# MolunSmartHomeKits_2021-06-21.net
KiCad netlist of a schematic drawn in EasyEDA
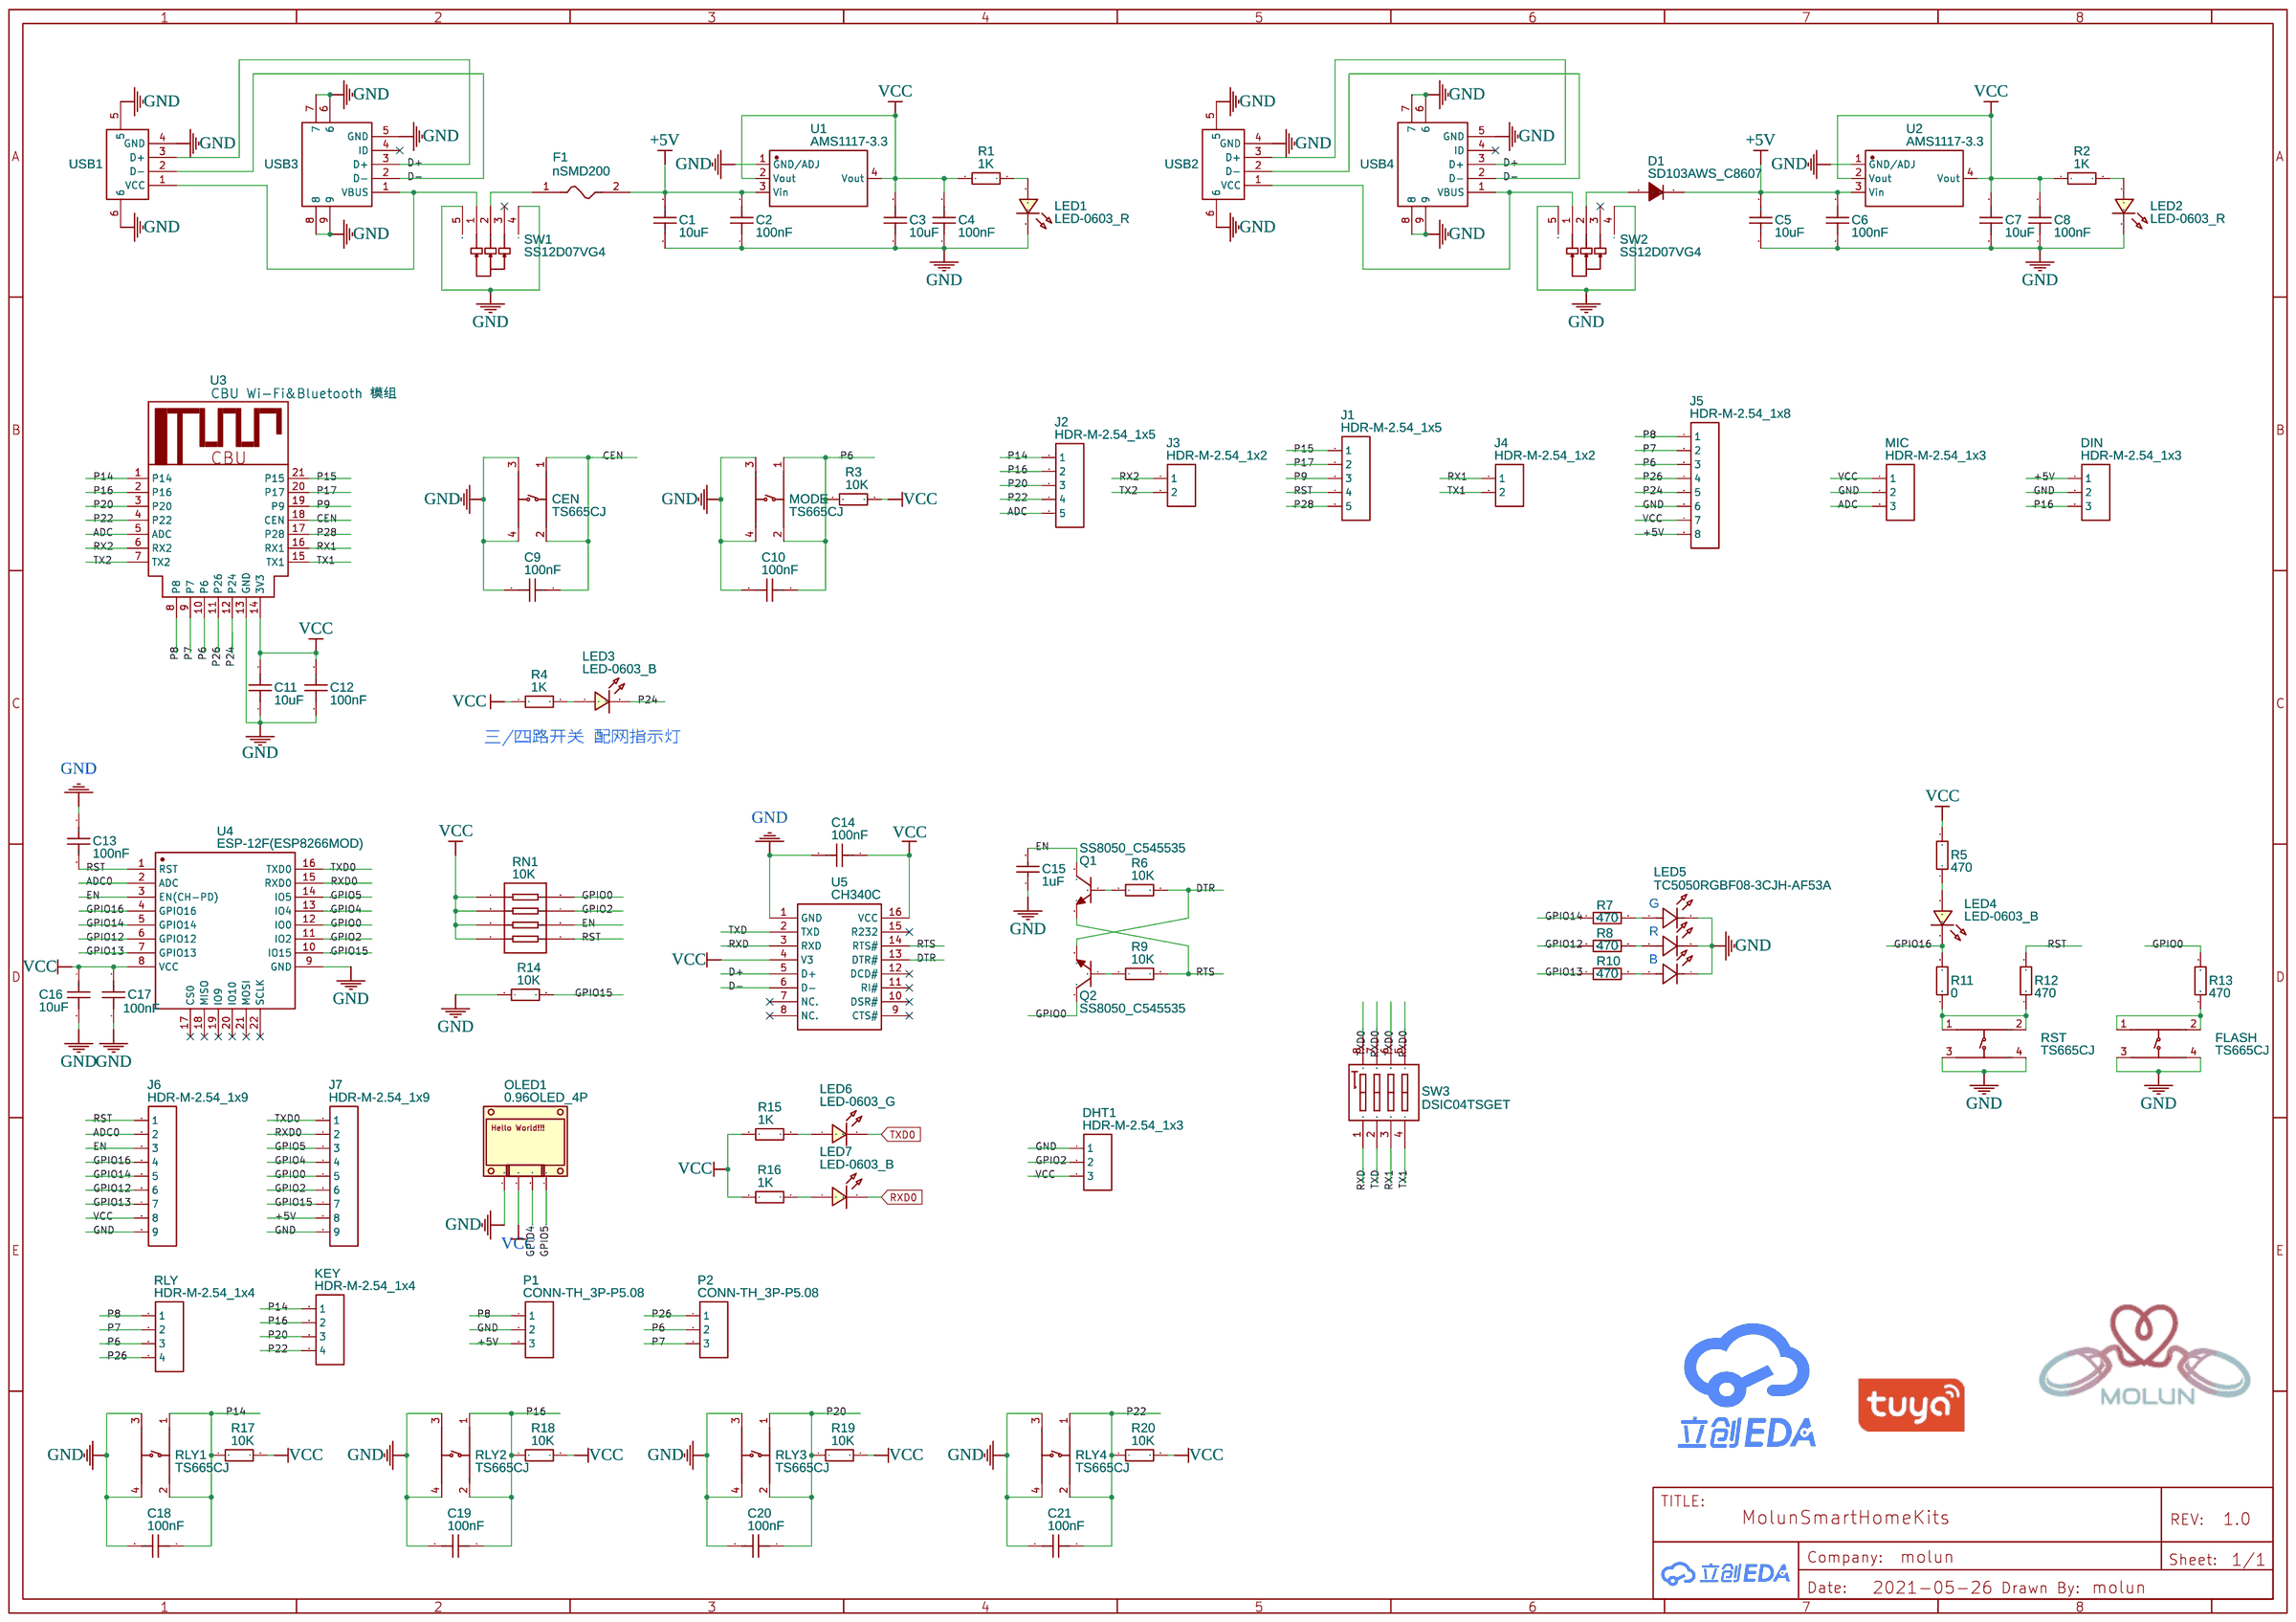
[diagram p0: MolunSmartHomeKits]
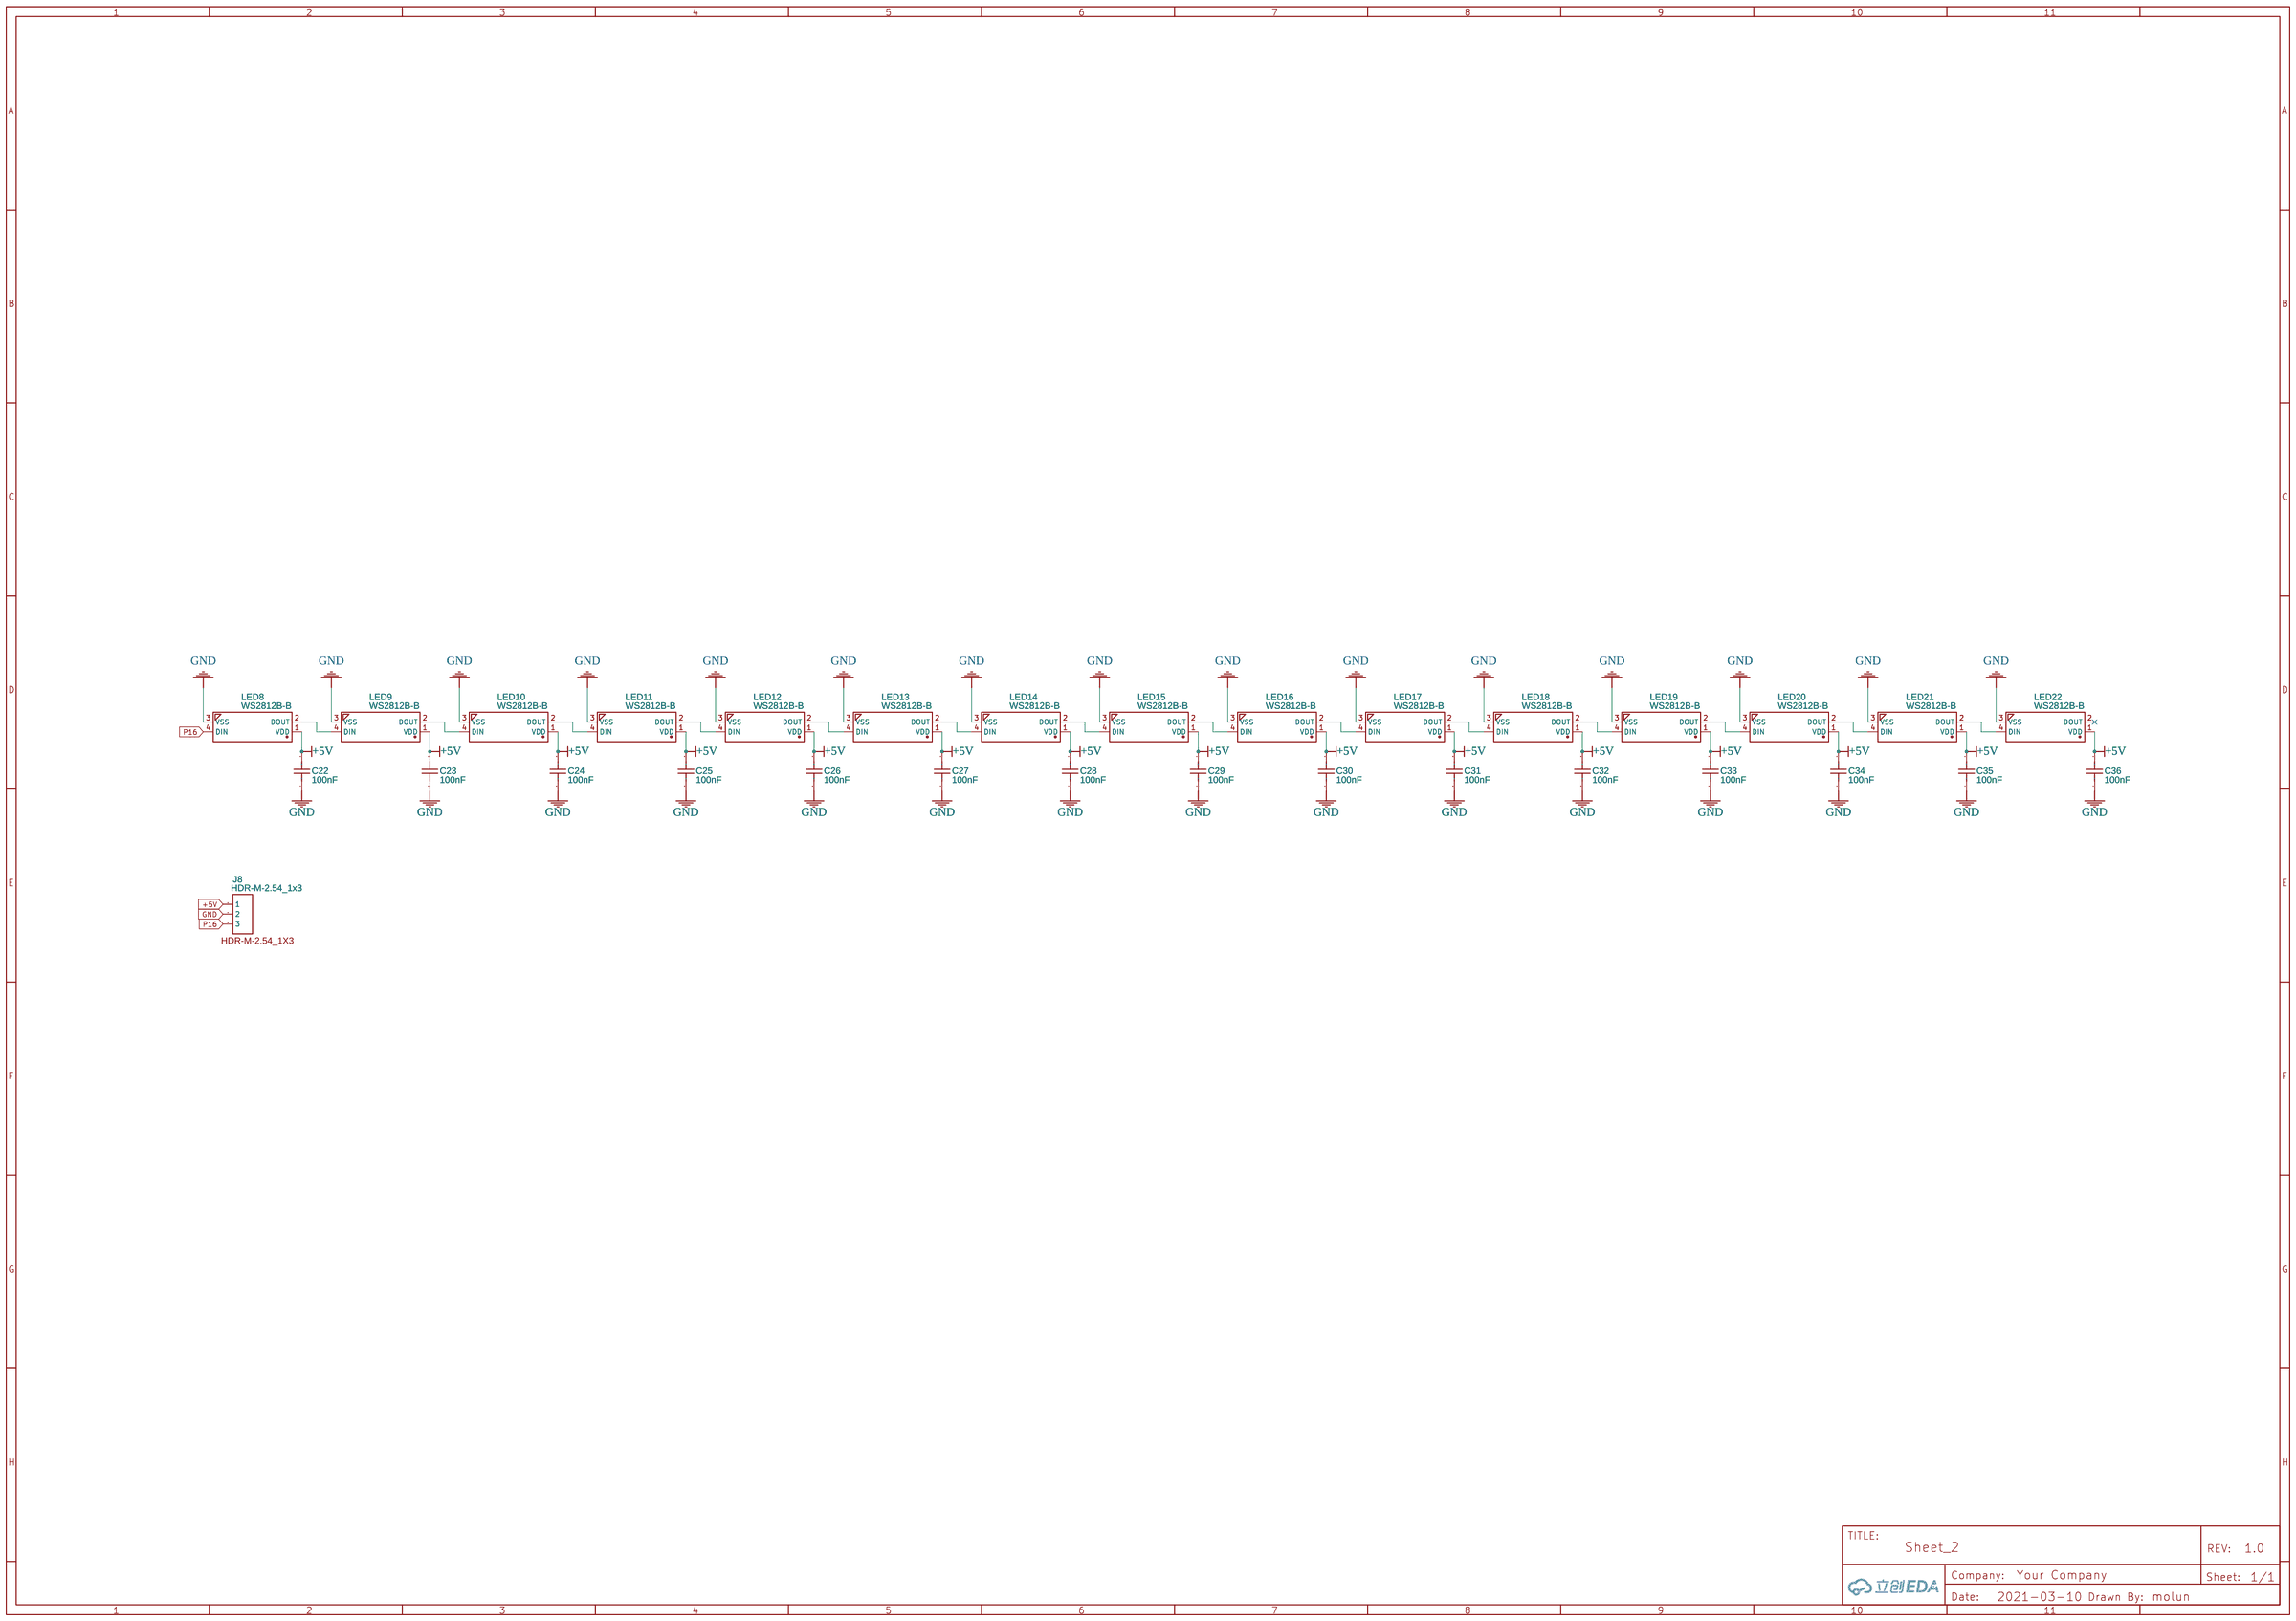
[diagram p1: 4合1_WS2812B圆环灯板]

(export (version "E")
  (design (tool "Eeschema 10.0.6"))
  (components
    (comp (ref "C1")
      (value "10uF")
      (fields
        (field (name "BOM_Manufacturer Part") "CC0603KRX5R6BB106")
        (field (name "BOM_Supplier Part") "C326057")
      )
      (libsource (lib "") (part "CC0603KRX5R6BB106"))
    )
    (comp (ref "C2")
      (value "100nF")
      (fields
        (field (name "BOM_Manufacturer Part") "AC0603KRX7R9BB104")
        (field (name "BOM_Supplier Part") "C149620")
      )
      (libsource (lib "") (part "AC0603KRX7R9BB104"))
    )
    (comp (ref "C3")
      (value "10uF")
      (fields
        (field (name "BOM_Manufacturer Part") "CC0603KRX5R6BB106")
        (field (name "BOM_Supplier Part") "C326057")
      )
      (libsource (lib "") (part "CC0603KRX5R6BB106"))
    )
    (comp (ref "C4")
      (value "100nF")
      (fields
        (field (name "BOM_Manufacturer Part") "AC0603KRX7R9BB104")
        (field (name "BOM_Supplier Part") "C149620")
      )
      (libsource (lib "") (part "AC0603KRX7R9BB104"))
    )
    (comp (ref "C5")
      (value "10uF")
      (fields
        (field (name "BOM_Manufacturer Part") "CC0603KRX5R6BB106")
        (field (name "BOM_Supplier Part") "C326057")
      )
      (libsource (lib "") (part "CC0603KRX5R6BB106"))
    )
    (comp (ref "C6")
      (value "100nF")
      (fields
        (field (name "BOM_Manufacturer Part") "AC0603KRX7R9BB104")
        (field (name "BOM_Supplier Part") "C149620")
      )
      (libsource (lib "") (part "AC0603KRX7R9BB104"))
    )
    (comp (ref "C7")
      (value "10uF")
      (fields
        (field (name "BOM_Manufacturer Part") "CC0603KRX5R6BB106")
        (field (name "BOM_Supplier Part") "C326057")
      )
      (libsource (lib "") (part "CC0603KRX5R6BB106"))
    )
    (comp (ref "C8")
      (value "100nF")
      (fields
        (field (name "BOM_Manufacturer Part") "AC0603KRX7R9BB104")
        (field (name "BOM_Supplier Part") "C149620")
      )
      (libsource (lib "") (part "AC0603KRX7R9BB104"))
    )
    (comp (ref "C9")
      (value "100nF")
      (fields
        (field (name "BOM_Manufacturer Part") "CC0603KRX7R7BB104")
        (field (name "BOM_Supplier Part") "C108079")
      )
      (libsource (lib "") (part "CC0603KRX7R7BB104_1"))
    )
    (comp (ref "C10")
      (value "100nF")
      (fields
        (field (name "BOM_Manufacturer Part") "CC0603KRX7R7BB104")
        (field (name "BOM_Supplier Part") "C108079")
      )
      (libsource (lib "") (part "CC0603KRX7R7BB104_1"))
    )
    (comp (ref "C11")
      (value "10uF")
      (fields
        (field (name "BOM_Manufacturer Part") "CL10A106MQ8NNNC")
        (field (name "BOM_Supplier Part") "C1691")
      )
      (libsource (lib "") (part "CL10A106MQ8NNNC"))
    )
    (comp (ref "C12")
      (value "100nF")
      (fields
        (field (name "BOM_Manufacturer Part") "CC0603KRX7R7BB104")
        (field (name "BOM_Supplier Part") "C108079")
      )
      (libsource (lib "") (part "CC0603KRX7R7BB104"))
    )
    (comp (ref "C13")
      (value "100nF")
      (fields
        (field (name "BOM_Manufacturer Part") "CC0603KRX7R7BB104")
        (field (name "BOM_Supplier Part") "C108079")
      )
      (libsource (lib "") (part "CC0603KRX7R7BB104_2"))
    )
    (comp (ref "C14")
      (value "100nF")
      (fields
        (field (name "BOM_Manufacturer Part") "AC0603KRX7R9BB104")
        (field (name "BOM_Supplier Part") "C149620")
      )
      (libsource (lib "") (part "AC0603KRX7R9BB104_1"))
    )
    (comp (ref "C15")
      (value "1uF")
      (fields
        (field (name "BOM_Manufacturer Part") "CC0603KRX5R7BB105")
        (field (name "BOM_Supplier Part") "C106215")
      )
      (libsource (lib "") (part "CC0603KRX5R7BB105"))
    )
    (comp (ref "C16")
      (value "10uF")
      (fields
        (field (name "BOM_Manufacturer Part") "CL10A106MQ8NNNC")
        (field (name "BOM_Supplier Part") "C1691")
      )
      (libsource (lib "") (part "CL10A106MQ8NNNC"))
    )
    (comp (ref "C17")
      (value "100nF")
      (fields
        (field (name "BOM_Manufacturer Part") "CC0603KRX7R7BB104")
        (field (name "BOM_Supplier Part") "C108079")
      )
      (libsource (lib "") (part "CC0603KRX7R7BB104"))
    )
    (comp (ref "C18")
      (value "100nF")
      (fields
        (field (name "BOM_Manufacturer Part") "CC0603KRX7R7BB104")
        (field (name "BOM_Supplier Part") "C108079")
      )
      (libsource (lib "") (part "CC0603KRX7R7BB104_1"))
    )
    (comp (ref "C19")
      (value "100nF")
      (fields
        (field (name "BOM_Manufacturer Part") "CC0603KRX7R7BB104")
        (field (name "BOM_Supplier Part") "C108079")
      )
      (libsource (lib "") (part "CC0603KRX7R7BB104_1"))
    )
    (comp (ref "C20")
      (value "100nF")
      (fields
        (field (name "BOM_Manufacturer Part") "CC0603KRX7R7BB104")
        (field (name "BOM_Supplier Part") "C108079")
      )
      (libsource (lib "") (part "CC0603KRX7R7BB104_1"))
    )
    (comp (ref "C21")
      (value "100nF")
      (fields
        (field (name "BOM_Manufacturer Part") "CC0603KRX7R7BB104")
        (field (name "BOM_Supplier Part") "C108079")
      )
      (libsource (lib "") (part "CC0603KRX7R7BB104_1"))
    )
    (comp (ref "CEN")
      (value "TS665CJ")
      (fields (field (name "BOM_Supplier Part") "C393938"))
      (libsource (lib "") (part "TS665CJ_2"))
    )
    (comp (ref "D1")
      (value "SD103AWS_C8607")
      (fields (field (name "BOM_Manufacturer Part") "SD103AWS") (field (name "BOM_Supplier Part") "C8607"))
      (libsource (lib "") (part "SD103AWS_C8607"))
    )
    (comp (ref "DHT1")
      (value "HDR-M-2.54_1x3")
      (fields (field (name "BOM_Supplier Part") "C180248"))
      (libsource (lib "") (part "HDR-M-2.54_1x3_2"))
    )
    (comp (ref "DIN")
      (value "HDR-M-2.54_1x3")
      (fields (field (name "BOM_Supplier Part") "C180248"))
      (libsource (lib "") (part "HDR-M-2.54_1x3_1"))
    )
    (comp (ref "F1")
      (value "nSMD200")
      (fields (field (name "BOM_Supplier Part") "C70085"))
      (libsource (lib "") (part "nSMD200"))
    )
    (comp (ref "FLASH")
      (value "TS665CJ")
      (fields (field (name "BOM_Supplier Part") "C393938"))
      (libsource (lib "") (part "TS665CJ_4"))
    )
    (comp (ref "J1")
      (value "HDR-M-2.54_1x5")
      (fields (field (name "BOM_Supplier Part") "C358687"))
      (libsource (lib "") (part "HDR-M-2.54_1x5"))
    )
    (comp (ref "J2")
      (value "HDR-M-2.54_1x5")
      (fields (field (name "BOM_Supplier Part") "C358687"))
      (libsource (lib "") (part "HDR-M-2.54_1x5"))
    )
    (comp (ref "J3")
      (value "HDR-M-2.54_1x2")
      (fields (field (name "BOM_Supplier Part") "C124375"))
      (libsource (lib "") (part "HDR-M-2.54_1x2"))
    )
    (comp (ref "J4")
      (value "HDR-M-2.54_1x2")
      (fields (field (name "BOM_Supplier Part") "C124375"))
      (libsource (lib "") (part "HDR-M-2.54_1x2"))
    )
    (comp (ref "J5")
      (value "HDR-M-2.54_1x8")
      (fields (field (name "BOM_Supplier Part") "C190820"))
      (libsource (lib "") (part "HDR-M-2.54_1x8"))
    )
    (comp (ref "J6")
      (value "HDR-M-2.54_1x9")
      (fields (field (name "BOM_Supplier Part") "C225484"))
      (libsource (lib "") (part "HDR-M-2.54_1x9"))
    )
    (comp (ref "J7")
      (value "HDR-M-2.54_1x9")
      (fields (field (name "BOM_Supplier Part") "C225484"))
      (libsource (lib "") (part "HDR-M-2.54_1x9"))
    )
    (comp (ref "KEY")
      (value "HDR-M-2.54_1x4")
      (fields (field (name "BOM_Supplier Part") "C124378"))
      (libsource (lib "") (part "HDR-M-2.54_1x4_1"))
    )
    (comp (ref "LED1")
      (value "LED-0603_R")
      (fields
        (field (name "BOM_Manufacturer Part") "19-217/R6C-AL1M2VY/3T")
        (field (name "BOM_Supplier Part") "C72044")
      )
      (libsource (lib "") (part "LED-0603_R"))
    )
    (comp (ref "LED2")
      (value "LED-0603_R")
      (fields
        (field (name "BOM_Manufacturer Part") "19-217/R6C-AL1M2VY/3T")
        (field (name "BOM_Supplier Part") "C72044")
      )
      (libsource (lib "") (part "LED-0603_R"))
    )
    (comp (ref "LED3")
      (value "LED-0603_B")
      (fields
        (field (name "BOM_Manufacturer Part") "19-217/BHC-ZL1M2RY/3T")
        (field (name "BOM_Supplier Part") "C72041")
      )
      (libsource (lib "") (part "LED-0603_B"))
    )
    (comp (ref "LED4")
      (value "LED-0603_B")
      (fields
        (field (name "BOM_Manufacturer Part") "19-217/BHC-ZL1M2RY/3T")
        (field (name "BOM_Supplier Part") "C72041")
      )
      (libsource (lib "") (part "LED-0603_B_1"))
    )
    (comp (ref "LED5")
      (value "TC5050RGBF08-3CJH-AF53A")
      (fields (field (name "BOM_Supplier Part") "C784540"))
      (libsource (lib "") (part "TC5050RGBF08-3CJH-AF53A"))
    )
    (comp (ref "LED6")
      (value "LED-0603_G")
      (fields
        (field (name "BOM_Manufacturer Part") "19-217/GHC-YR1S2/3T")
        (field (name "BOM_Supplier Part") "C72043")
      )
      (libsource (lib "") (part "LED-0603_G"))
    )
    (comp (ref "LED7")
      (value "LED-0603_B")
      (fields
        (field (name "BOM_Manufacturer Part") "19-217/BHC-ZL1M2RY/3T")
        (field (name "BOM_Supplier Part") "C72041")
      )
      (libsource (lib "") (part "LED-0603_B"))
    )
    (comp (ref "MIC")
      (value "HDR-M-2.54_1x3")
      (fields (field (name "BOM_Supplier Part") "C180248"))
      (libsource (lib "") (part "HDR-M-2.54_1x3"))
    )
    (comp (ref "MODE")
      (value "TS665CJ")
      (fields (field (name "BOM_Supplier Part") "C393938"))
      (libsource (lib "") (part "TS665CJ_1"))
    )
    (comp (ref "OLED1") (value "0.96OLED_4P") (libsource (lib "") (part "0.96OLED_4P")))
    (comp (ref "P1") (value "CONN-TH_3P-P5.08") (libsource (lib "") (part "CONN-TH_3P-P5.08")))
    (comp (ref "P2") (value "CONN-TH_3P-P5.08") (libsource (lib "") (part "CONN-TH_3P-P5.08")))
    (comp (ref "Q1")
      (value "SS8050_C545535")
      (fields (field (name "BOM_Manufacturer Part") "SS8050") (field (name "BOM_Supplier Part") "C545535"))
      (libsource (lib "") (part "SS8050_C545535"))
    )
    (comp (ref "Q2")
      (value "SS8050_C545535")
      (fields (field (name "BOM_Manufacturer Part") "SS8050") (field (name "BOM_Supplier Part") "C545535"))
      (libsource (lib "") (part "SS8050_C545535_1"))
    )
    (comp (ref "R1")
      (value "1K")
      (fields
        (field (name "BOM_Manufacturer Part") "0603WAF1001T5E")
        (field (name "BOM_Supplier Part") "C21190")
      )
      (libsource (lib "") (part "0603WAF1001T5E"))
    )
    (comp (ref "R2")
      (value "1K")
      (fields
        (field (name "BOM_Manufacturer Part") "0603WAF1001T5E")
        (field (name "BOM_Supplier Part") "C21190")
      )
      (libsource (lib "") (part "0603WAF1001T5E"))
    )
    (comp (ref "R3")
      (value "10K")
      (fields
        (field (name "BOM_Manufacturer Part") "0603WAJ0103T5E")
        (field (name "BOM_Supplier Part") "C15401")
      )
      (libsource (lib "") (part "0603WAJ0103T5E"))
    )
    (comp (ref "R4")
      (value "1K")
      (fields
        (field (name "BOM_Manufacturer Part") "0603WAF1001T5E")
        (field (name "BOM_Supplier Part") "C21190")
      )
      (libsource (lib "") (part "0603WAF1001T5E"))
    )
    (comp (ref "R5")
      (value "470")
      (fields
        (field (name "BOM_Manufacturer Part") "0603WAF4700T5E")
        (field (name "BOM_Supplier Part") "C23179")
      )
      (libsource (lib "") (part "0603WAF4700T5E"))
    )
    (comp (ref "R6")
      (value "10K")
      (fields
        (field (name "BOM_Manufacturer Part") "0603WAF1002T5E")
        (field (name "BOM_Supplier Part") "C25804")
      )
      (libsource (lib "") (part "0603WAF1002T5E"))
    )
    (comp (ref "R7")
      (value "470")
      (fields
        (field (name "BOM_Manufacturer Part") "0603WAF4700T5E")
        (field (name "BOM_Supplier Part") "C23179")
      )
      (libsource (lib "") (part "0603WAF4700T5E_1"))
    )
    (comp (ref "R8")
      (value "470")
      (fields
        (field (name "BOM_Manufacturer Part") "0603WAF4700T5E")
        (field (name "BOM_Supplier Part") "C23179")
      )
      (libsource (lib "") (part "0603WAF4700T5E_1"))
    )
    (comp (ref "R9")
      (value "10K")
      (fields
        (field (name "BOM_Manufacturer Part") "0603WAF1002T5E")
        (field (name "BOM_Supplier Part") "C25804")
      )
      (libsource (lib "") (part "0603WAF1002T5E"))
    )
    (comp (ref "R10")
      (value "470")
      (fields
        (field (name "BOM_Manufacturer Part") "0603WAF4700T5E")
        (field (name "BOM_Supplier Part") "C23179")
      )
      (libsource (lib "") (part "0603WAF4700T5E_1"))
    )
    (comp (ref "R11")
      (value "0")
      (fields
        (field (name "BOM_Manufacturer Part") "AECR0603F0000K9")
        (field (name "BOM_Supplier Part") "C328332")
      )
      (libsource (lib "") (part "AECR0603F0000K9"))
    )
    (comp (ref "R12")
      (value "470")
      (fields
        (field (name "BOM_Manufacturer Part") "0603WAF4700T5E")
        (field (name "BOM_Supplier Part") "C23179")
      )
      (libsource (lib "") (part "0603WAF4700T5E"))
    )
    (comp (ref "R13")
      (value "470")
      (fields
        (field (name "BOM_Manufacturer Part") "0603WAF4700T5E")
        (field (name "BOM_Supplier Part") "C23179")
      )
      (libsource (lib "") (part "0603WAF4700T5E"))
    )
    (comp (ref "R14")
      (value "10K")
      (fields
        (field (name "BOM_Manufacturer Part") "0603WAF1002T5E")
        (field (name "BOM_Supplier Part") "C25804")
      )
      (libsource (lib "") (part "0603WAF1002T5E"))
    )
    (comp (ref "R15")
      (value "1K")
      (fields
        (field (name "BOM_Manufacturer Part") "0603WAF1001T5E")
        (field (name "BOM_Supplier Part") "C21190")
      )
      (libsource (lib "") (part "0603WAF1001T5E"))
    )
    (comp (ref "R16")
      (value "1K")
      (fields
        (field (name "BOM_Manufacturer Part") "0603WAF1001T5E")
        (field (name "BOM_Supplier Part") "C21190")
      )
      (libsource (lib "") (part "0603WAF1001T5E"))
    )
    (comp (ref "R17")
      (value "10K")
      (fields
        (field (name "BOM_Manufacturer Part") "0603WAJ0103T5E")
        (field (name "BOM_Supplier Part") "C15401")
      )
      (libsource (lib "") (part "0603WAJ0103T5E"))
    )
    (comp (ref "R18")
      (value "10K")
      (fields
        (field (name "BOM_Manufacturer Part") "0603WAJ0103T5E")
        (field (name "BOM_Supplier Part") "C15401")
      )
      (libsource (lib "") (part "0603WAJ0103T5E"))
    )
    (comp (ref "R19")
      (value "10K")
      (fields
        (field (name "BOM_Manufacturer Part") "0603WAJ0103T5E")
        (field (name "BOM_Supplier Part") "C15401")
      )
      (libsource (lib "") (part "0603WAJ0103T5E"))
    )
    (comp (ref "R20")
      (value "10K")
      (fields
        (field (name "BOM_Manufacturer Part") "0603WAJ0103T5E")
        (field (name "BOM_Supplier Part") "C15401")
      )
      (libsource (lib "") (part "0603WAJ0103T5E"))
    )
    (comp (ref "RLY")
      (value "HDR-M-2.54_1x4")
      (fields (field (name "BOM_Supplier Part") "C124378"))
      (libsource (lib "") (part "HDR-M-2.54_1x4"))
    )
    (comp (ref "RLY1")
      (value "TS665CJ")
      (fields (field (name "BOM_Supplier Part") "C393938"))
      (libsource (lib "") (part "TS665CJ"))
    )
    (comp (ref "RLY2")
      (value "TS665CJ")
      (fields (field (name "BOM_Supplier Part") "C393938"))
      (libsource (lib "") (part "TS665CJ"))
    )
    (comp (ref "RLY3")
      (value "TS665CJ")
      (fields (field (name "BOM_Supplier Part") "C393938"))
      (libsource (lib "") (part "TS665CJ"))
    )
    (comp (ref "RLY4")
      (value "TS665CJ")
      (fields (field (name "BOM_Supplier Part") "C393938"))
      (libsource (lib "") (part "TS665CJ"))
    )
    (comp (ref "RN1")
      (value "10K")
      (fields
        (field (name "BOM_Manufacturer Part") "4D03WGJ0103T5E")
        (field (name "BOM_Supplier Part") "C29718")
      )
      (libsource (lib "") (part "4D03WGJ0103T5E"))
    )
    (comp (ref "RST")
      (value "TS665CJ")
      (fields (field (name "BOM_Supplier Part") "C393938"))
      (libsource (lib "") (part "TS665CJ_3"))
    )
    (comp (ref "SW1")
      (value "SS12D07VG4")
      (fields (field (name "BOM_Supplier Part") "C431546"))
      (libsource (lib "") (part "SS12D07VG4"))
    )
    (comp (ref "SW2")
      (value "SS12D07VG4")
      (fields (field (name "BOM_Supplier Part") "C431546"))
      (libsource (lib "") (part "SS12D07VG4"))
    )
    (comp (ref "SW3")
      (value "DSIC04TSGET")
      (fields (field (name "BOM_Supplier Part") "C126850"))
      (libsource (lib "") (part "DSIC04TSGET"))
    )
    (comp (ref "U1")
      (value "AMS1117-3.3")
      (fields (field (name "BOM_Supplier Part") "C6186"))
      (libsource (lib "") (part "AMS1117-3.3"))
    )
    (comp (ref "U2")
      (value "AMS1117-3.3")
      (fields (field (name "BOM_Supplier Part") "C6186"))
      (libsource (lib "") (part "AMS1117-3.3"))
    )
    (comp (ref "U3")
      (value "CBU Wi-Fi&Bluetooth 模组")
      (libsource (lib "") (part "CBU Wi-Fi&amp;Bluetooth 模组"))
    )
    (comp (ref "U4")
      (value "ESP-12F(ESP8266MOD)")
      (fields (field (name "BOM_Supplier Part") "C82891"))
      (libsource (lib "") (part "ESP-12F(ESP8266MOD)"))
    )
    (comp (ref "U5")
      (value "CH340C")
      (fields (field (name "BOM_Supplier Part") "C84681"))
      (libsource (lib "") (part "CH340C"))
    )
    (comp (ref "USB1")
      (value "U217-04XN-XXR84")
      (fields (field (name "BOM_Supplier Part") "C319178"))
      (libsource (lib "") (part "U217-04XN-XXR84"))
    )
    (comp (ref "USB2")
      (value "U217-04XN-XXR84")
      (fields (field (name "BOM_Supplier Part") "C319178"))
      (libsource (lib "") (part "U217-04XN-XXR84"))
    )
    (comp (ref "USB3")
      (value "U254-051T-4BH83-F1S")
      (fields (field (name "BOM_Supplier Part") "C397452"))
      (libsource (lib "") (part "U254-051T-4BH83-F1S"))
    )
    (comp (ref "USB4")
      (value "U254-051T-4BH83-F1S")
      (fields (field (name "BOM_Supplier Part") "C397452"))
      (libsource (lib "") (part "U254-051T-4BH83-F1S"))
    )
    (comp (ref "C22")
      (value "100nF")
      (fields
        (field (name "BOM_Manufacturer Part") "CC0603KRX7R7BB104")
        (field (name "BOM_Supplier Part") "C108079")
      )
      (libsource (lib "") (part "CC0603KRX7R7BB104"))
    )
    (comp (ref "C23")
      (value "100nF")
      (fields
        (field (name "BOM_Manufacturer Part") "CC0603KRX7R7BB104")
        (field (name "BOM_Supplier Part") "C108079")
      )
      (libsource (lib "") (part "CC0603KRX7R7BB104"))
    )
    (comp (ref "C24")
      (value "100nF")
      (fields
        (field (name "BOM_Manufacturer Part") "CC0603KRX7R7BB104")
        (field (name "BOM_Supplier Part") "C108079")
      )
      (libsource (lib "") (part "CC0603KRX7R7BB104"))
    )
    (comp (ref "C25")
      (value "100nF")
      (fields
        (field (name "BOM_Manufacturer Part") "CC0603KRX7R7BB104")
        (field (name "BOM_Supplier Part") "C108079")
      )
      (libsource (lib "") (part "CC0603KRX7R7BB104"))
    )
    (comp (ref "C26")
      (value "100nF")
      (fields
        (field (name "BOM_Manufacturer Part") "CC0603KRX7R7BB104")
        (field (name "BOM_Supplier Part") "C108079")
      )
      (libsource (lib "") (part "CC0603KRX7R7BB104"))
    )
    (comp (ref "C27")
      (value "100nF")
      (fields
        (field (name "BOM_Manufacturer Part") "CC0603KRX7R7BB104")
        (field (name "BOM_Supplier Part") "C108079")
      )
      (libsource (lib "") (part "CC0603KRX7R7BB104"))
    )
    (comp (ref "C28")
      (value "100nF")
      (fields
        (field (name "BOM_Manufacturer Part") "CC0603KRX7R7BB104")
        (field (name "BOM_Supplier Part") "C108079")
      )
      (libsource (lib "") (part "CC0603KRX7R7BB104"))
    )
    (comp (ref "C29")
      (value "100nF")
      (fields
        (field (name "BOM_Manufacturer Part") "CC0603KRX7R7BB104")
        (field (name "BOM_Supplier Part") "C108079")
      )
      (libsource (lib "") (part "CC0603KRX7R7BB104"))
    )
    (comp (ref "C30")
      (value "100nF")
      (fields
        (field (name "BOM_Manufacturer Part") "CC0603KRX7R7BB104")
        (field (name "BOM_Supplier Part") "C108079")
      )
      (libsource (lib "") (part "CC0603KRX7R7BB104"))
    )
    (comp (ref "C31")
      (value "100nF")
      (fields
        (field (name "BOM_Manufacturer Part") "CC0603KRX7R7BB104")
        (field (name "BOM_Supplier Part") "C108079")
      )
      (libsource (lib "") (part "CC0603KRX7R7BB104"))
    )
    (comp (ref "C32")
      (value "100nF")
      (fields
        (field (name "BOM_Manufacturer Part") "CC0603KRX7R7BB104")
        (field (name "BOM_Supplier Part") "C108079")
      )
      (libsource (lib "") (part "CC0603KRX7R7BB104"))
    )
    (comp (ref "C33")
      (value "100nF")
      (fields
        (field (name "BOM_Manufacturer Part") "CC0603KRX7R7BB104")
        (field (name "BOM_Supplier Part") "C108079")
      )
      (libsource (lib "") (part "CC0603KRX7R7BB104"))
    )
    (comp (ref "C34")
      (value "100nF")
      (fields
        (field (name "BOM_Manufacturer Part") "CC0603KRX7R7BB104")
        (field (name "BOM_Supplier Part") "C108079")
      )
      (libsource (lib "") (part "CC0603KRX7R7BB104"))
    )
    (comp (ref "C35")
      (value "100nF")
      (fields
        (field (name "BOM_Manufacturer Part") "CC0603KRX7R7BB104")
        (field (name "BOM_Supplier Part") "C108079")
      )
      (libsource (lib "") (part "CC0603KRX7R7BB104"))
    )
    (comp (ref "C36")
      (value "100nF")
      (fields
        (field (name "BOM_Manufacturer Part") "CC0603KRX7R7BB104")
        (field (name "BOM_Supplier Part") "C108079")
      )
      (libsource (lib "") (part "CC0603KRX7R7BB104"))
    )
    (comp (ref "J8")
      (value "HDR-M-2.54_1x3")
      (fields (field (name "BOM_Supplier Part") "C180248"))
      (libsource (lib "") (part "HDR-M-2.54_1x3"))
    )
    (comp (ref "LED8")
      (value "WS2812B-B")
      (fields (field (name "BOM_Supplier Part") "C114586"))
      (libsource (lib "") (part "WS2812B-B"))
    )
    (comp (ref "LED9")
      (value "WS2812B-B")
      (fields (field (name "BOM_Supplier Part") "C114586"))
      (libsource (lib "") (part "WS2812B-B"))
    )
    (comp (ref "LED10")
      (value "WS2812B-B")
      (fields (field (name "BOM_Supplier Part") "C114586"))
      (libsource (lib "") (part "WS2812B-B"))
    )
    (comp (ref "LED11")
      (value "WS2812B-B")
      (fields (field (name "BOM_Supplier Part") "C114586"))
      (libsource (lib "") (part "WS2812B-B"))
    )
    (comp (ref "LED12")
      (value "WS2812B-B")
      (fields (field (name "BOM_Supplier Part") "C114586"))
      (libsource (lib "") (part "WS2812B-B"))
    )
    (comp (ref "LED13")
      (value "WS2812B-B")
      (fields (field (name "BOM_Supplier Part") "C114586"))
      (libsource (lib "") (part "WS2812B-B"))
    )
    (comp (ref "LED14")
      (value "WS2812B-B")
      (fields (field (name "BOM_Supplier Part") "C114586"))
      (libsource (lib "") (part "WS2812B-B"))
    )
    (comp (ref "LED15")
      (value "WS2812B-B")
      (fields (field (name "BOM_Supplier Part") "C114586"))
      (libsource (lib "") (part "WS2812B-B"))
    )
    (comp (ref "LED16")
      (value "WS2812B-B")
      (fields (field (name "BOM_Supplier Part") "C114586"))
      (libsource (lib "") (part "WS2812B-B"))
    )
    (comp (ref "LED17")
      (value "WS2812B-B")
      (fields (field (name "BOM_Supplier Part") "C114586"))
      (libsource (lib "") (part "WS2812B-B"))
    )
    (comp (ref "LED18")
      (value "WS2812B-B")
      (fields (field (name "BOM_Supplier Part") "C114586"))
      (libsource (lib "") (part "WS2812B-B"))
    )
    (comp (ref "LED19")
      (value "WS2812B-B")
      (fields (field (name "BOM_Supplier Part") "C114586"))
      (libsource (lib "") (part "WS2812B-B"))
    )
    (comp (ref "LED20")
      (value "WS2812B-B")
      (fields (field (name "BOM_Supplier Part") "C114586"))
      (libsource (lib "") (part "WS2812B-B"))
    )
    (comp (ref "LED21")
      (value "WS2812B-B")
      (fields (field (name "BOM_Supplier Part") "C114586"))
      (libsource (lib "") (part "WS2812B-B"))
    )
    (comp (ref "LED22")
      (value "WS2812B-B")
      (fields (field (name "BOM_Supplier Part") "C114586"))
      (libsource (lib "") (part "WS2812B-B"))
    )
  )
  (nets
    (net (code "1") (name "+5V") (class "Default")
      (node (ref "C1") (pin "2") (pinfunction "2_2") (pintype "unspecified"))
      (node (ref "C2") (pin "2") (pinfunction "2_2") (pintype "unspecified"))
      (node (ref "C22") (pin "2") (pinfunction "2_2") (pintype "unspecified"))
      (node (ref "C23") (pin "2") (pinfunction "2_2") (pintype "unspecified"))
      (node (ref "C24") (pin "2") (pinfunction "2_2") (pintype "unspecified"))
      (node (ref "C25") (pin "2") (pinfunction "2_2") (pintype "unspecified"))
      (node (ref "C26") (pin "2") (pinfunction "2_2") (pintype "unspecified"))
      (node (ref "C27") (pin "2") (pinfunction "2_2") (pintype "unspecified"))
      (node (ref "C28") (pin "2") (pinfunction "2_2") (pintype "unspecified"))
      (node (ref "C29") (pin "2") (pinfunction "2_2") (pintype "unspecified"))
      (node (ref "C30") (pin "2") (pinfunction "2_2") (pintype "unspecified"))
      (node (ref "C31") (pin "2") (pinfunction "2_2") (pintype "unspecified"))
      (node (ref "C32") (pin "2") (pinfunction "2_2") (pintype "unspecified"))
      (node (ref "C33") (pin "2") (pinfunction "2_2") (pintype "unspecified"))
      (node (ref "C34") (pin "2") (pinfunction "2_2") (pintype "unspecified"))
      (node (ref "C35") (pin "2") (pinfunction "2_2") (pintype "unspecified"))
      (node (ref "C36") (pin "2") (pinfunction "2_2") (pintype "unspecified"))
      (node (ref "C5") (pin "2") (pinfunction "2_2") (pintype "unspecified"))
      (node (ref "C6") (pin "2") (pinfunction "2_2") (pintype "unspecified"))
      (node (ref "D1") (pin "1") (pinfunction "C_1") (pintype "unspecified"))
      (node (ref "DIN") (pin "1") (pinfunction "1_1") (pintype "input"))
      (node (ref "F1") (pin "2") (pinfunction "2_2") (pintype "unspecified"))
      (node (ref "J5") (pin "8") (pinfunction "8_8") (pintype "unspecified"))
      (node (ref "J7") (pin "8") (pinfunction "8_8") (pintype "unspecified"))
      (node (ref "J8") (pin "1") (pinfunction "1_1") (pintype "input"))
      (node (ref "LED10") (pin "1") (pinfunction "VDD_1") (pintype "unspecified"))
      (node (ref "LED11") (pin "1") (pinfunction "VDD_1") (pintype "unspecified"))
      (node (ref "LED12") (pin "1") (pinfunction "VDD_1") (pintype "unspecified"))
      (node (ref "LED13") (pin "1") (pinfunction "VDD_1") (pintype "unspecified"))
      (node (ref "LED14") (pin "1") (pinfunction "VDD_1") (pintype "unspecified"))
      (node (ref "LED15") (pin "1") (pinfunction "VDD_1") (pintype "unspecified"))
      (node (ref "LED16") (pin "1") (pinfunction "VDD_1") (pintype "unspecified"))
      (node (ref "LED17") (pin "1") (pinfunction "VDD_1") (pintype "unspecified"))
      (node (ref "LED18") (pin "1") (pinfunction "VDD_1") (pintype "unspecified"))
      (node (ref "LED19") (pin "1") (pinfunction "VDD_1") (pintype "unspecified"))
      (node (ref "LED20") (pin "1") (pinfunction "VDD_1") (pintype "unspecified"))
      (node (ref "LED21") (pin "1") (pinfunction "VDD_1") (pintype "unspecified"))
      (node (ref "LED22") (pin "1") (pinfunction "VDD_1") (pintype "unspecified"))
      (node (ref "LED8") (pin "1") (pinfunction "VDD_1") (pintype "unspecified"))
      (node (ref "LED9") (pin "1") (pinfunction "VDD_1") (pintype "unspecified"))
      (node (ref "P1") (pin "3") (pinfunction "3_3") (pintype "unspecified"))
      (node (ref "U1") (pin "3") (pinfunction "Vin_3") (pintype "unspecified"))
      (node (ref "U2") (pin "3") (pinfunction "Vin_3") (pintype "unspecified"))
    )
    (net (code "2") (name "ADC") (class "Default")
      (node (ref "J2") (pin "5") (pinfunction "5_5") (pintype "unspecified"))
      (node (ref "MIC") (pin "3") (pinfunction "3_3") (pintype "input"))
      (node (ref "U3") (pin "5") (pinfunction "ADC_5") (pintype "bidirectional"))
    )
    (net (code "3") (name "ADC0") (class "Default")
      (node (ref "J6") (pin "2") (pinfunction "2_2") (pintype "unspecified"))
      (node (ref "U4") (pin "2") (pinfunction "ADC_2") (pintype "unspecified"))
    )
    (net (code "4") (name "CEN") (class "Default")
      (node (ref "C9") (pin "1") (pinfunction "1_1") (pintype "unspecified"))
      (node (ref "CEN") (pin "1") (pinfunction "A_1") (pintype "unspecified"))
      (node (ref "CEN") (pin "2") (pinfunction "B_2") (pintype "unspecified"))
      (node (ref "U3") (pin "18") (pinfunction "CEN_18") (pintype "bidirectional"))
    )
    (net (code "5") (name "D+") (class "Default")
      (node (ref "U5") (pin "5") (pinfunction "D+_5") (pintype "unspecified"))
      (node (ref "USB1") (pin "3") (pinfunction "D+_3") (pintype "unspecified"))
      (node (ref "USB2") (pin "3") (pinfunction "D+_3") (pintype "unspecified"))
      (node (ref "USB3") (pin "3") (pinfunction "D+_3") (pintype "unspecified"))
      (node (ref "USB4") (pin "3") (pinfunction "D+_3") (pintype "unspecified"))
    )
    (net (code "6") (name "D-") (class "Default")
      (node (ref "U5") (pin "6") (pinfunction "D-_6") (pintype "unspecified"))
      (node (ref "USB1") (pin "2") (pinfunction "D-_2") (pintype "unspecified"))
      (node (ref "USB2") (pin "2") (pinfunction "D-_2") (pintype "unspecified"))
      (node (ref "USB3") (pin "2") (pinfunction "D-_2") (pintype "unspecified"))
      (node (ref "USB4") (pin "2") (pinfunction "D-_2") (pintype "unspecified"))
    )
    (net (code "7") (name "DTR") (class "Default")
      (node (ref "Q2") (pin "2") (pinfunction "E_2") (pintype "input"))
      (node (ref "R6") (pin "2") (pinfunction "2_2") (pintype "input"))
      (node (ref "U5") (pin "13") (pinfunction "DTR#_13") (pintype "unspecified"))
    )
    (net (code "8") (name "EN") (class "Default")
      (node (ref "C15") (pin "2") (pinfunction "2_2") (pintype "input"))
      (node (ref "J6") (pin "3") (pinfunction "3_3") (pintype "unspecified"))
      (node (ref "Q1") (pin "3") (pinfunction "C_3") (pintype "input"))
      (node (ref "RN1") (pin "6") (pinfunction "6_6") (pintype "input"))
      (node (ref "U4") (pin "3") (pinfunction "EN(CH-PD)_3") (pintype "unspecified"))
    )
    (net (code "9") (name "GND") (class "Default")
      (node (ref "C1") (pin "1") (pinfunction "1_1") (pintype "unspecified"))
      (node (ref "C10") (pin "2") (pinfunction "2_2") (pintype "unspecified"))
      (node (ref "C11") (pin "2") (pinfunction "2_2") (pintype "unspecified"))
      (node (ref "C12") (pin "1") (pinfunction "1_1") (pintype "unspecified"))
      (node (ref "C13") (pin "1") (pinfunction "1_1") (pintype "unspecified"))
      (node (ref "C14") (pin "2") (pinfunction "2_2") (pintype "unspecified"))
      (node (ref "C15") (pin "1") (pinfunction "1_1") (pintype "input"))
      (node (ref "C16") (pin "2") (pinfunction "2_2") (pintype "unspecified"))
      (node (ref "C17") (pin "1") (pinfunction "1_1") (pintype "unspecified"))
      (node (ref "C18") (pin "2") (pinfunction "2_2") (pintype "unspecified"))
      (node (ref "C19") (pin "2") (pinfunction "2_2") (pintype "unspecified"))
      (node (ref "C2") (pin "1") (pinfunction "1_1") (pintype "unspecified"))
      (node (ref "C20") (pin "2") (pinfunction "2_2") (pintype "unspecified"))
      (node (ref "C21") (pin "2") (pinfunction "2_2") (pintype "unspecified"))
      (node (ref "C22") (pin "1") (pinfunction "1_1") (pintype "unspecified"))
      (node (ref "C23") (pin "1") (pinfunction "1_1") (pintype "unspecified"))
      (node (ref "C24") (pin "1") (pinfunction "1_1") (pintype "unspecified"))
      (node (ref "C25") (pin "1") (pinfunction "1_1") (pintype "unspecified"))
      (node (ref "C26") (pin "1") (pinfunction "1_1") (pintype "unspecified"))
      (node (ref "C27") (pin "1") (pinfunction "1_1") (pintype "unspecified"))
      (node (ref "C28") (pin "1") (pinfunction "1_1") (pintype "unspecified"))
      (node (ref "C29") (pin "1") (pinfunction "1_1") (pintype "unspecified"))
      (node (ref "C3") (pin "1") (pinfunction "1_1") (pintype "unspecified"))
      (node (ref "C30") (pin "1") (pinfunction "1_1") (pintype "unspecified"))
      (node (ref "C31") (pin "1") (pinfunction "1_1") (pintype "unspecified"))
      (node (ref "C32") (pin "1") (pinfunction "1_1") (pintype "unspecified"))
      (node (ref "C33") (pin "1") (pinfunction "1_1") (pintype "unspecified"))
      (node (ref "C34") (pin "1") (pinfunction "1_1") (pintype "unspecified"))
      (node (ref "C35") (pin "1") (pinfunction "1_1") (pintype "unspecified"))
      (node (ref "C36") (pin "1") (pinfunction "1_1") (pintype "unspecified"))
      (node (ref "C4") (pin "1") (pinfunction "1_1") (pintype "unspecified"))
      (node (ref "C5") (pin "1") (pinfunction "1_1") (pintype "unspecified"))
      (node (ref "C6") (pin "1") (pinfunction "1_1") (pintype "unspecified"))
      (node (ref "C7") (pin "1") (pinfunction "1_1") (pintype "unspecified"))
      (node (ref "C8") (pin "1") (pinfunction "1_1") (pintype "unspecified"))
      (node (ref "C9") (pin "2") (pinfunction "2_2") (pintype "unspecified"))
      (node (ref "CEN") (pin "3") (pinfunction "C_3") (pintype "unspecified"))
      (node (ref "CEN") (pin "4") (pinfunction "D_4") (pintype "unspecified"))
      (node (ref "DHT1") (pin "1") (pinfunction "1_1") (pintype "input"))
      (node (ref "DIN") (pin "2") (pinfunction "2_2") (pintype "input"))
      (node (ref "FLASH") (pin "3") (pinfunction "C_3") (pintype "unspecified"))
      (node (ref "FLASH") (pin "4") (pinfunction "D_4") (pintype "unspecified"))
      (node (ref "J5") (pin "6") (pinfunction "6_6") (pintype "unspecified"))
      (node (ref "J6") (pin "9") (pinfunction "9_9") (pintype "unspecified"))
      (node (ref "J7") (pin "9") (pinfunction "9_9") (pintype "unspecified"))
      (node (ref "J8") (pin "2") (pinfunction "2_2") (pintype "input"))
      (node (ref "LED1") (pin "2") (pinfunction "2_2") (pintype "unspecified"))
      (node (ref "LED10") (pin "3") (pinfunction "VSS_3") (pintype "unspecified"))
      (node (ref "LED11") (pin "3") (pinfunction "VSS_3") (pintype "unspecified"))
      (node (ref "LED12") (pin "3") (pinfunction "VSS_3") (pintype "unspecified"))
      (node (ref "LED13") (pin "3") (pinfunction "VSS_3") (pintype "unspecified"))
      (node (ref "LED14") (pin "3") (pinfunction "VSS_3") (pintype "unspecified"))
      (node (ref "LED15") (pin "3") (pinfunction "VSS_3") (pintype "unspecified"))
      (node (ref "LED16") (pin "3") (pinfunction "VSS_3") (pintype "unspecified"))
      (node (ref "LED17") (pin "3") (pinfunction "VSS_3") (pintype "unspecified"))
      (node (ref "LED18") (pin "3") (pinfunction "VSS_3") (pintype "unspecified"))
      (node (ref "LED19") (pin "3") (pinfunction "VSS_3") (pintype "unspecified"))
      (node (ref "LED2") (pin "2") (pinfunction "2_2") (pintype "unspecified"))
      (node (ref "LED20") (pin "3") (pinfunction "VSS_3") (pintype "unspecified"))
      (node (ref "LED21") (pin "3") (pinfunction "VSS_3") (pintype "unspecified"))
      (node (ref "LED22") (pin "3") (pinfunction "VSS_3") (pintype "unspecified"))
      (node (ref "LED5") (pin "4") (pinfunction "-_4") (pintype "unspecified"))
      (node (ref "LED5") (pin "5") (pinfunction "-_5") (pintype "unspecified"))
      (node (ref "LED5") (pin "6") (pinfunction "-_6") (pintype "unspecified"))
      (node (ref "LED8") (pin "3") (pinfunction "VSS_3") (pintype "unspecified"))
      (node (ref "LED9") (pin "3") (pinfunction "VSS_3") (pintype "unspecified"))
      (node (ref "MIC") (pin "2") (pinfunction "2_2") (pintype "input"))
      (node (ref "MODE") (pin "3") (pinfunction "C_3") (pintype "unspecified"))
      (node (ref "MODE") (pin "4") (pinfunction "D_4") (pintype "unspecified"))
      (node (ref "OLED1") (pin "1") (pinfunction "1_1") (pintype "unspecified"))
      (node (ref "P1") (pin "2") (pinfunction "2_2") (pintype "unspecified"))
      (node (ref "R14") (pin "1") (pinfunction "1_1") (pintype "input"))
      (node (ref "RLY1") (pin "3") (pinfunction "C_3") (pintype "unspecified"))
      (node (ref "RLY1") (pin "4") (pinfunction "D_4") (pintype "unspecified"))
      (node (ref "RLY2") (pin "3") (pinfunction "C_3") (pintype "unspecified"))
      (node (ref "RLY2") (pin "4") (pinfunction "D_4") (pintype "unspecified"))
      (node (ref "RLY3") (pin "3") (pinfunction "C_3") (pintype "unspecified"))
      (node (ref "RLY3") (pin "4") (pinfunction "D_4") (pintype "unspecified"))
      (node (ref "RLY4") (pin "3") (pinfunction "C_3") (pintype "unspecified"))
      (node (ref "RLY4") (pin "4") (pinfunction "D_4") (pintype "unspecified"))
      (node (ref "RST") (pin "3") (pinfunction "C_3") (pintype "unspecified"))
      (node (ref "RST") (pin "4") (pinfunction "D_4") (pintype "unspecified"))
      (node (ref "SW1") (pin "4") (pinfunction "4_4") (pintype "unspecified"))
      (node (ref "SW1") (pin "5") (pinfunction "5_5") (pintype "unspecified"))
      (node (ref "SW2") (pin "4") (pinfunction "4_4") (pintype "unspecified"))
      (node (ref "SW2") (pin "5") (pinfunction "5_5") (pintype "unspecified"))
      (node (ref "U1") (pin "1") (pinfunction "GND/ADJ_1") (pintype "unspecified"))
      (node (ref "U2") (pin "1") (pinfunction "GND/ADJ_1") (pintype "unspecified"))
      (node (ref "U3") (pin "13") (pinfunction "GND_13") (pintype "passive"))
      (node (ref "U4") (pin "9") (pinfunction "GND_9") (pintype "unspecified"))
      (node (ref "U5") (pin "1") (pinfunction "GND_1") (pintype "unspecified"))
      (node (ref "USB1") (pin "4") (pinfunction "GND_4") (pintype "unspecified"))
      (node (ref "USB1") (pin "5") (pinfunction "5_5") (pintype "unspecified"))
      (node (ref "USB1") (pin "6") (pinfunction "6_6") (pintype "unspecified"))
      (node (ref "USB2") (pin "4") (pinfunction "GND_4") (pintype "unspecified"))
      (node (ref "USB2") (pin "5") (pinfunction "5_5") (pintype "unspecified"))
      (node (ref "USB2") (pin "6") (pinfunction "6_6") (pintype "unspecified"))
      (node (ref "USB3") (pin "5") (pinfunction "GND_5") (pintype "unspecified"))
      (node (ref "USB3") (pin "6") (pinfunction "6_6") (pintype "unspecified"))
      (node (ref "USB3") (pin "7") (pinfunction "7_7") (pintype "unspecified"))
      (node (ref "USB3") (pin "8") (pinfunction "8_8") (pintype "unspecified"))
      (node (ref "USB3") (pin "9") (pinfunction "9_9") (pintype "unspecified"))
      (node (ref "USB4") (pin "5") (pinfunction "GND_5") (pintype "unspecified"))
      (node (ref "USB4") (pin "6") (pinfunction "6_6") (pintype "unspecified"))
      (node (ref "USB4") (pin "7") (pinfunction "7_7") (pintype "unspecified"))
      (node (ref "USB4") (pin "8") (pinfunction "8_8") (pintype "unspecified"))
      (node (ref "USB4") (pin "9") (pinfunction "9_9") (pintype "unspecified"))
    )
    (net (code "10") (name "GPIO0") (class "Default")
      (node (ref "J7") (pin "5") (pinfunction "5_5") (pintype "unspecified"))
      (node (ref "Q2") (pin "3") (pinfunction "C_3") (pintype "input"))
      (node (ref "R13") (pin "2") (pinfunction "2_2") (pintype "input"))
      (node (ref "RN1") (pin "8") (pinfunction "8_8") (pintype "input"))
      (node (ref "U4") (pin "12") (pinfunction "IO0_12") (pintype "unspecified"))
    )
    (net (code "11") (name "GPIO2") (class "Default")
      (node (ref "DHT1") (pin "2") (pinfunction "2_2") (pintype "input"))
      (node (ref "J7") (pin "6") (pinfunction "6_6") (pintype "unspecified"))
      (node (ref "RN1") (pin "7") (pinfunction "7_7") (pintype "input"))
      (node (ref "U4") (pin "11") (pinfunction "IO2_11") (pintype "unspecified"))
    )
    (net (code "12") (name "GPIO4") (class "Default")
      (node (ref "J7") (pin "4") (pinfunction "4_4") (pintype "unspecified"))
      (node (ref "OLED1") (pin "3") (pinfunction "3_3") (pintype "unspecified"))
      (node (ref "U4") (pin "13") (pinfunction "IO4_13") (pintype "unspecified"))
    )
    (net (code "13") (name "GPIO5") (class "Default")
      (node (ref "J7") (pin "3") (pinfunction "3_3") (pintype "unspecified"))
      (node (ref "OLED1") (pin "4") (pinfunction "4_4") (pintype "unspecified"))
      (node (ref "U4") (pin "14") (pinfunction "IO5_14") (pintype "unspecified"))
    )
    (net (code "14") (name "GPIO12") (class "Default")
      (node (ref "J6") (pin "6") (pinfunction "6_6") (pintype "unspecified"))
      (node (ref "R8") (pin "1") (pinfunction "1_1") (pintype "input"))
      (node (ref "U4") (pin "6") (pinfunction "GPIO12_6") (pintype "unspecified"))
    )
    (net (code "15") (name "GPIO13") (class "Default")
      (node (ref "J6") (pin "7") (pinfunction "7_7") (pintype "unspecified"))
      (node (ref "R10") (pin "1") (pinfunction "1_1") (pintype "input"))
      (node (ref "U4") (pin "7") (pinfunction "GPIO13_7") (pintype "unspecified"))
    )
    (net (code "16") (name "GPIO14") (class "Default")
      (node (ref "J6") (pin "5") (pinfunction "5_5") (pintype "unspecified"))
      (node (ref "R7") (pin "1") (pinfunction "1_1") (pintype "input"))
      (node (ref "U4") (pin "5") (pinfunction "GPIO14_5") (pintype "unspecified"))
    )
    (net (code "17") (name "GPIO15") (class "Default")
      (node (ref "J7") (pin "7") (pinfunction "7_7") (pintype "unspecified"))
      (node (ref "R14") (pin "2") (pinfunction "2_2") (pintype "input"))
      (node (ref "U4") (pin "10") (pinfunction "IO15_10") (pintype "unspecified"))
    )
    (net (code "18") (name "GPIO16") (class "Default")
      (node (ref "J6") (pin "4") (pinfunction "4_4") (pintype "unspecified"))
      (node (ref "LED4") (pin "2") (pinfunction "2_2") (pintype "unspecified"))
      (node (ref "R11") (pin "2") (pinfunction "2_2") (pintype "unspecified"))
      (node (ref "U4") (pin "4") (pinfunction "GPIO16_4") (pintype "unspecified"))
    )
    (net (code "19") (name "Net-(D1-A)") (class "Default")
      (node (ref "D1") (pin "2") (pinfunction "A_2") (pintype "unspecified"))
      (node (ref "SW2") (pin "2") (pinfunction "2_2") (pintype "unspecified"))
    )
    (net (code "20") (name "Net-(F1-Pad1)") (class "Default")
      (node (ref "F1") (pin "1") (pinfunction "1_1") (pintype "unspecified"))
      (node (ref "SW1") (pin "2") (pinfunction "2_2") (pintype "unspecified"))
    )
    (net (code "21") (name "Net-(FLASH-A)") (class "Default")
      (node (ref "FLASH") (pin "1") (pinfunction "A_1") (pintype "unspecified"))
      (node (ref "FLASH") (pin "2") (pinfunction "B_2") (pintype "unspecified"))
      (node (ref "R13") (pin "1") (pinfunction "1_1") (pintype "input"))
    )
    (net (code "22") (name "Net-(LED1-Pad1)") (class "Default")
      (node (ref "LED1") (pin "1") (pinfunction "1_1") (pintype "unspecified"))
      (node (ref "R1") (pin "2") (pinfunction "2_2") (pintype "input"))
    )
    (net (code "23") (name "Net-(LED2-Pad1)") (class "Default")
      (node (ref "LED2") (pin "1") (pinfunction "1_1") (pintype "unspecified"))
      (node (ref "R2") (pin "2") (pinfunction "2_2") (pintype "input"))
    )
    (net (code "24") (name "Net-(LED3-Pad1)") (class "Default")
      (node (ref "LED3") (pin "1") (pinfunction "1_1") (pintype "unspecified"))
      (node (ref "R4") (pin "2") (pinfunction "2_2") (pintype "input"))
    )
    (net (code "25") (name "Net-(LED4-Pad1)") (class "Default")
      (node (ref "LED4") (pin "1") (pinfunction "1_1") (pintype "unspecified"))
      (node (ref "R5") (pin "1") (pinfunction "1_1") (pintype "input"))
    )
    (net (code "26") (name "Net-(LED5-+-Pad1)") (class "Default")
      (node (ref "LED5") (pin "1") (pinfunction "+_1") (pintype "unspecified"))
      (node (ref "R7") (pin "2") (pinfunction "2_2") (pintype "input"))
    )
    (net (code "27") (name "Net-(LED5-+-Pad2)") (class "Default")
      (node (ref "LED5") (pin "2") (pinfunction "+_2") (pintype "unspecified"))
      (node (ref "R8") (pin "2") (pinfunction "2_2") (pintype "input"))
    )
    (net (code "28") (name "Net-(LED5-+-Pad3)") (class "Default")
      (node (ref "LED5") (pin "3") (pinfunction "+_3") (pintype "unspecified"))
      (node (ref "R10") (pin "2") (pinfunction "2_2") (pintype "input"))
    )
    (net (code "29") (name "Net-(LED6-Pad1)") (class "Default")
      (node (ref "LED6") (pin "1") (pinfunction "1_1") (pintype "unspecified"))
      (node (ref "R15") (pin "2") (pinfunction "2_2") (pintype "input"))
    )
    (net (code "30") (name "Net-(LED7-Pad1)") (class "Default")
      (node (ref "LED7") (pin "1") (pinfunction "1_1") (pintype "unspecified"))
      (node (ref "R16") (pin "2") (pinfunction "2_2") (pintype "input"))
    )
    (net (code "31") (name "Net-(LED8-DOUT)") (class "Default")
      (node (ref "LED8") (pin "2") (pinfunction "DOUT_2") (pintype "unspecified"))
      (node (ref "LED9") (pin "4") (pinfunction "DIN_4") (pintype "unspecified"))
    )
    (net (code "32") (name "Net-(LED10-DIN)") (class "Default")
      (node (ref "LED10") (pin "4") (pinfunction "DIN_4") (pintype "unspecified"))
      (node (ref "LED9") (pin "2") (pinfunction "DOUT_2") (pintype "unspecified"))
    )
    (net (code "33") (name "Net-(LED10-DOUT)") (class "Default")
      (node (ref "LED10") (pin "2") (pinfunction "DOUT_2") (pintype "unspecified"))
      (node (ref "LED11") (pin "4") (pinfunction "DIN_4") (pintype "unspecified"))
    )
    (net (code "34") (name "Net-(LED11-DOUT)") (class "Default")
      (node (ref "LED11") (pin "2") (pinfunction "DOUT_2") (pintype "unspecified"))
      (node (ref "LED12") (pin "4") (pinfunction "DIN_4") (pintype "unspecified"))
    )
    (net (code "35") (name "Net-(LED12-DOUT)") (class "Default")
      (node (ref "LED12") (pin "2") (pinfunction "DOUT_2") (pintype "unspecified"))
      (node (ref "LED13") (pin "4") (pinfunction "DIN_4") (pintype "unspecified"))
    )
    (net (code "36") (name "Net-(LED13-DOUT)") (class "Default")
      (node (ref "LED13") (pin "2") (pinfunction "DOUT_2") (pintype "unspecified"))
      (node (ref "LED14") (pin "4") (pinfunction "DIN_4") (pintype "unspecified"))
    )
    (net (code "37") (name "Net-(LED14-DOUT)") (class "Default")
      (node (ref "LED14") (pin "2") (pinfunction "DOUT_2") (pintype "unspecified"))
      (node (ref "LED15") (pin "4") (pinfunction "DIN_4") (pintype "unspecified"))
    )
    (net (code "38") (name "Net-(LED15-DOUT)") (class "Default")
      (node (ref "LED15") (pin "2") (pinfunction "DOUT_2") (pintype "unspecified"))
      (node (ref "LED16") (pin "4") (pinfunction "DIN_4") (pintype "unspecified"))
    )
    (net (code "39") (name "Net-(LED16-DOUT)") (class "Default")
      (node (ref "LED16") (pin "2") (pinfunction "DOUT_2") (pintype "unspecified"))
      (node (ref "LED17") (pin "4") (pinfunction "DIN_4") (pintype "unspecified"))
    )
    (net (code "40") (name "Net-(LED17-DOUT)") (class "Default")
      (node (ref "LED17") (pin "2") (pinfunction "DOUT_2") (pintype "unspecified"))
      (node (ref "LED18") (pin "4") (pinfunction "DIN_4") (pintype "unspecified"))
    )
    (net (code "41") (name "Net-(LED18-DOUT)") (class "Default")
      (node (ref "LED18") (pin "2") (pinfunction "DOUT_2") (pintype "unspecified"))
      (node (ref "LED19") (pin "4") (pinfunction "DIN_4") (pintype "unspecified"))
    )
    (net (code "42") (name "Net-(LED19-DOUT)") (class "Default")
      (node (ref "LED19") (pin "2") (pinfunction "DOUT_2") (pintype "unspecified"))
      (node (ref "LED20") (pin "4") (pinfunction "DIN_4") (pintype "unspecified"))
    )
    (net (code "43") (name "Net-(LED20-DOUT)") (class "Default")
      (node (ref "LED20") (pin "2") (pinfunction "DOUT_2") (pintype "unspecified"))
      (node (ref "LED21") (pin "4") (pinfunction "DIN_4") (pintype "unspecified"))
    )
    (net (code "44") (name "Net-(LED21-DOUT)") (class "Default")
      (node (ref "LED21") (pin "2") (pinfunction "DOUT_2") (pintype "unspecified"))
      (node (ref "LED22") (pin "4") (pinfunction "DIN_4") (pintype "unspecified"))
    )
    (net (code "45") (name "Net-(Q1-B)") (class "Default")
      (node (ref "Q1") (pin "1") (pinfunction "B_1") (pintype "input"))
      (node (ref "R6") (pin "1") (pinfunction "1_1") (pintype "input"))
    )
    (net (code "46") (name "Net-(Q2-B)") (class "Default")
      (node (ref "Q2") (pin "1") (pinfunction "B_1") (pintype "input"))
      (node (ref "R9") (pin "1") (pinfunction "1_1") (pintype "input"))
    )
    (net (code "47") (name "Net-(RST-A)") (class "Default")
      (node (ref "R11") (pin "1") (pinfunction "1_1") (pintype "unspecified"))
      (node (ref "R12") (pin "1") (pinfunction "1_1") (pintype "input"))
      (node (ref "RST") (pin "1") (pinfunction "A_1") (pintype "unspecified"))
      (node (ref "RST") (pin "2") (pinfunction "B_2") (pintype "unspecified"))
    )
    (net (code "48") (name "Net-(USB1-VCC)") (class "Default")
      (node (ref "SW1") (pin "1") (pinfunction "1_1") (pintype "unspecified"))
      (node (ref "USB1") (pin "1") (pinfunction "VCC_1") (pintype "unspecified"))
      (node (ref "USB3") (pin "1") (pinfunction "VBUS_1") (pintype "unspecified"))
    )
    (net (code "49") (name "Net-(USB2-VCC)") (class "Default")
      (node (ref "SW2") (pin "1") (pinfunction "1_1") (pintype "unspecified"))
      (node (ref "USB2") (pin "1") (pinfunction "VCC_1") (pintype "unspecified"))
      (node (ref "USB4") (pin "1") (pinfunction "VBUS_1") (pintype "unspecified"))
    )
    (net (code "50") (name "P6") (class "Default")
      (node (ref "C10") (pin "1") (pinfunction "1_1") (pintype "unspecified"))
      (node (ref "J5") (pin "3") (pinfunction "3_3") (pintype "unspecified"))
      (node (ref "MODE") (pin "1") (pinfunction "A_1") (pintype "unspecified"))
      (node (ref "MODE") (pin "2") (pinfunction "B_2") (pintype "unspecified"))
      (node (ref "P2") (pin "2") (pinfunction "2_2") (pintype "unspecified"))
      (node (ref "R3") (pin "1") (pinfunction "1_1") (pintype "input"))
      (node (ref "RLY") (pin "3") (pinfunction "3_3") (pintype "unspecified"))
      (node (ref "U3") (pin "10") (pinfunction "P6_10") (pintype "bidirectional"))
    )
    (net (code "51") (name "P7") (class "Default")
      (node (ref "J5") (pin "2") (pinfunction "2_2") (pintype "unspecified"))
      (node (ref "P2") (pin "3") (pinfunction "3_3") (pintype "unspecified"))
      (node (ref "RLY") (pin "2") (pinfunction "2_2") (pintype "unspecified"))
      (node (ref "U3") (pin "9") (pinfunction "P7_9") (pintype "bidirectional"))
    )
    (net (code "52") (name "P8") (class "Default")
      (node (ref "J5") (pin "1") (pinfunction "1_1") (pintype "unspecified"))
      (node (ref "P1") (pin "1") (pinfunction "1_1") (pintype "unspecified"))
      (node (ref "RLY") (pin "1") (pinfunction "1_1") (pintype "unspecified"))
      (node (ref "U3") (pin "8") (pinfunction "P8_8") (pintype "bidirectional"))
    )
    (net (code "53") (name "P9") (class "Default")
      (node (ref "J1") (pin "3") (pinfunction "3_3") (pintype "unspecified"))
      (node (ref "U3") (pin "19") (pinfunction "P9_19") (pintype "bidirectional"))
    )
    (net (code "54") (name "P14") (class "Default")
      (node (ref "C18") (pin "1") (pinfunction "1_1") (pintype "unspecified"))
      (node (ref "J2") (pin "1") (pinfunction "1_1") (pintype "unspecified"))
      (node (ref "KEY") (pin "1") (pinfunction "1_1") (pintype "unspecified"))
      (node (ref "R17") (pin "1") (pinfunction "1_1") (pintype "input"))
      (node (ref "RLY1") (pin "1") (pinfunction "A_1") (pintype "unspecified"))
      (node (ref "RLY1") (pin "2") (pinfunction "B_2") (pintype "unspecified"))
      (node (ref "U3") (pin "1") (pinfunction "P14_1") (pintype "bidirectional"))
    )
    (net (code "55") (name "P15") (class "Default")
      (node (ref "J1") (pin "1") (pinfunction "1_1") (pintype "unspecified"))
      (node (ref "U3") (pin "21") (pinfunction "P15_21") (pintype "bidirectional"))
    )
    (net (code "56") (name "P16") (class "Default")
      (node (ref "C19") (pin "1") (pinfunction "1_1") (pintype "unspecified"))
      (node (ref "DIN") (pin "3") (pinfunction "3_3") (pintype "input"))
      (node (ref "J2") (pin "2") (pinfunction "2_2") (pintype "unspecified"))
      (node (ref "J8") (pin "3") (pinfunction "3_3") (pintype "input"))
      (node (ref "KEY") (pin "2") (pinfunction "2_2") (pintype "unspecified"))
      (node (ref "LED8") (pin "4") (pinfunction "DIN_4") (pintype "unspecified"))
      (node (ref "R18") (pin "1") (pinfunction "1_1") (pintype "input"))
      (node (ref "RLY2") (pin "1") (pinfunction "A_1") (pintype "unspecified"))
      (node (ref "RLY2") (pin "2") (pinfunction "B_2") (pintype "unspecified"))
      (node (ref "U3") (pin "2") (pinfunction "P16_2") (pintype "bidirectional"))
    )
    (net (code "57") (name "P17") (class "Default")
      (node (ref "J1") (pin "2") (pinfunction "2_2") (pintype "unspecified"))
      (node (ref "U3") (pin "20") (pinfunction "P17_20") (pintype "bidirectional"))
    )
    (net (code "58") (name "P20") (class "Default")
      (node (ref "C20") (pin "1") (pinfunction "1_1") (pintype "unspecified"))
      (node (ref "J2") (pin "3") (pinfunction "3_3") (pintype "unspecified"))
      (node (ref "KEY") (pin "3") (pinfunction "3_3") (pintype "unspecified"))
      (node (ref "R19") (pin "1") (pinfunction "1_1") (pintype "input"))
      (node (ref "RLY3") (pin "1") (pinfunction "A_1") (pintype "unspecified"))
      (node (ref "RLY3") (pin "2") (pinfunction "B_2") (pintype "unspecified"))
      (node (ref "U3") (pin "3") (pinfunction "P20_3") (pintype "bidirectional"))
    )
    (net (code "59") (name "P22") (class "Default")
      (node (ref "C21") (pin "1") (pinfunction "1_1") (pintype "unspecified"))
      (node (ref "J2") (pin "4") (pinfunction "4_4") (pintype "unspecified"))
      (node (ref "KEY") (pin "4") (pinfunction "4_4") (pintype "unspecified"))
      (node (ref "R20") (pin "1") (pinfunction "1_1") (pintype "input"))
      (node (ref "RLY4") (pin "1") (pinfunction "A_1") (pintype "unspecified"))
      (node (ref "RLY4") (pin "2") (pinfunction "B_2") (pintype "unspecified"))
      (node (ref "U3") (pin "4") (pinfunction "P22_4") (pintype "bidirectional"))
    )
    (net (code "60") (name "P24") (class "Default")
      (node (ref "J5") (pin "5") (pinfunction "5_5") (pintype "unspecified"))
      (node (ref "LED3") (pin "2") (pinfunction "2_2") (pintype "unspecified"))
      (node (ref "U3") (pin "12") (pinfunction "P24_12") (pintype "bidirectional"))
    )
    (net (code "61") (name "P26") (class "Default")
      (node (ref "J5") (pin "4") (pinfunction "4_4") (pintype "unspecified"))
      (node (ref "P2") (pin "1") (pinfunction "1_1") (pintype "unspecified"))
      (node (ref "RLY") (pin "4") (pinfunction "4_4") (pintype "unspecified"))
      (node (ref "U3") (pin "11") (pinfunction "P26_11") (pintype "bidirectional"))
    )
    (net (code "62") (name "P28") (class "Default")
      (node (ref "J1") (pin "5") (pinfunction "5_5") (pintype "unspecified"))
      (node (ref "U3") (pin "17") (pinfunction "P28_17") (pintype "bidirectional"))
    )
    (net (code "63") (name "RST") (class "Default")
      (node (ref "C13") (pin "2") (pinfunction "2_2") (pintype "unspecified"))
      (node (ref "J1") (pin "4") (pinfunction "4_4") (pintype "unspecified"))
      (node (ref "J6") (pin "1") (pinfunction "1_1") (pintype "unspecified"))
      (node (ref "R12") (pin "2") (pinfunction "2_2") (pintype "input"))
      (node (ref "RN1") (pin "5") (pinfunction "5_5") (pintype "input"))
      (node (ref "U4") (pin "1") (pinfunction "RST_1") (pintype "unspecified"))
    )
    (net (code "64") (name "RTS") (class "Default")
      (node (ref "Q1") (pin "2") (pinfunction "E_2") (pintype "input"))
      (node (ref "R9") (pin "2") (pinfunction "2_2") (pintype "input"))
      (node (ref "U5") (pin "14") (pinfunction "RTS#_14") (pintype "unspecified"))
    )
    (net (code "65") (name "RX1") (class "Default")
      (node (ref "J4") (pin "1") (pinfunction "1_1") (pintype "unspecified"))
      (node (ref "SW3") (pin "3") (pinfunction "A3_3") (pintype "input"))
      (node (ref "U3") (pin "16") (pinfunction "RX1_16") (pintype "bidirectional"))
    )
    (net (code "66") (name "RX2") (class "Default")
      (node (ref "J3") (pin "1") (pinfunction "1_1") (pintype "unspecified"))
      (node (ref "U3") (pin "6") (pinfunction "RX2_6") (pintype "bidirectional"))
    )
    (net (code "67") (name "RXD") (class "Default")
      (node (ref "SW3") (pin "1") (pinfunction "A1_1") (pintype "input"))
      (node (ref "U5") (pin "3") (pinfunction "RXD_3") (pintype "unspecified"))
    )
    (net (code "68") (name "RXD0") (class "Default")
      (node (ref "J7") (pin "2") (pinfunction "2_2") (pintype "unspecified"))
      (node (ref "LED7") (pin "2") (pinfunction "2_2") (pintype "unspecified"))
      (node (ref "SW3") (pin "5") (pinfunction "B4_5") (pintype "input"))
      (node (ref "SW3") (pin "7") (pinfunction "B2_7") (pintype "input"))
      (node (ref "U4") (pin "15") (pinfunction "RXD0_15") (pintype "unspecified"))
    )
    (net (code "69") (name "TX1") (class "Default")
      (node (ref "J4") (pin "2") (pinfunction "2_2") (pintype "unspecified"))
      (node (ref "SW3") (pin "4") (pinfunction "A4_4") (pintype "input"))
      (node (ref "U3") (pin "15") (pinfunction "TX1_15") (pintype "bidirectional"))
    )
    (net (code "70") (name "TX2") (class "Default")
      (node (ref "J3") (pin "2") (pinfunction "2_2") (pintype "unspecified"))
      (node (ref "U3") (pin "7") (pinfunction "TX2_7") (pintype "bidirectional"))
    )
    (net (code "71") (name "TXD") (class "Default")
      (node (ref "SW3") (pin "2") (pinfunction "A2_2") (pintype "input"))
      (node (ref "U5") (pin "2") (pinfunction "TXD_2") (pintype "unspecified"))
    )
    (net (code "72") (name "TXD0") (class "Default")
      (node (ref "J7") (pin "1") (pinfunction "1_1") (pintype "unspecified"))
      (node (ref "LED6") (pin "2") (pinfunction "2_2") (pintype "unspecified"))
      (node (ref "SW3") (pin "6") (pinfunction "B3_6") (pintype "input"))
      (node (ref "SW3") (pin "8") (pinfunction "B1_8") (pintype "input"))
      (node (ref "U4") (pin "16") (pinfunction "TXD0_16") (pintype "unspecified"))
    )
    (net (code "73") (name "VCC") (class "Default")
      (node (ref "C11") (pin "1") (pinfunction "1_1") (pintype "unspecified"))
      (node (ref "C12") (pin "2") (pinfunction "2_2") (pintype "unspecified"))
      (node (ref "C14") (pin "1") (pinfunction "1_1") (pintype "unspecified"))
      (node (ref "C16") (pin "1") (pinfunction "1_1") (pintype "unspecified"))
      (node (ref "C17") (pin "2") (pinfunction "2_2") (pintype "unspecified"))
      (node (ref "C3") (pin "2") (pinfunction "2_2") (pintype "unspecified"))
      (node (ref "C4") (pin "2") (pinfunction "2_2") (pintype "unspecified"))
      (node (ref "C7") (pin "2") (pinfunction "2_2") (pintype "unspecified"))
      (node (ref "C8") (pin "2") (pinfunction "2_2") (pintype "unspecified"))
      (node (ref "DHT1") (pin "3") (pinfunction "3_3") (pintype "input"))
      (node (ref "J5") (pin "7") (pinfunction "7_7") (pintype "unspecified"))
      (node (ref "J6") (pin "8") (pinfunction "8_8") (pintype "unspecified"))
      (node (ref "MIC") (pin "1") (pinfunction "1_1") (pintype "input"))
      (node (ref "OLED1") (pin "2") (pinfunction "2_2") (pintype "unspecified"))
      (node (ref "R1") (pin "1") (pinfunction "1_1") (pintype "input"))
      (node (ref "R15") (pin "1") (pinfunction "1_1") (pintype "input"))
      (node (ref "R16") (pin "1") (pinfunction "1_1") (pintype "input"))
      (node (ref "R17") (pin "2") (pinfunction "2_2") (pintype "input"))
      (node (ref "R18") (pin "2") (pinfunction "2_2") (pintype "input"))
      (node (ref "R19") (pin "2") (pinfunction "2_2") (pintype "input"))
      (node (ref "R2") (pin "1") (pinfunction "1_1") (pintype "input"))
      (node (ref "R20") (pin "2") (pinfunction "2_2") (pintype "input"))
      (node (ref "R3") (pin "2") (pinfunction "2_2") (pintype "input"))
      (node (ref "R4") (pin "1") (pinfunction "1_1") (pintype "input"))
      (node (ref "R5") (pin "2") (pinfunction "2_2") (pintype "input"))
      (node (ref "RN1") (pin "1") (pinfunction "1_1") (pintype "input"))
      (node (ref "RN1") (pin "2") (pinfunction "2_2") (pintype "input"))
      (node (ref "RN1") (pin "3") (pinfunction "3_3") (pintype "input"))
      (node (ref "RN1") (pin "4") (pinfunction "4_4") (pintype "input"))
      (node (ref "U1") (pin "2") (pinfunction "Vout_2") (pintype "unspecified"))
      (node (ref "U1") (pin "4") (pinfunction "Vout_4") (pintype "unspecified"))
      (node (ref "U2") (pin "2") (pinfunction "Vout_2") (pintype "unspecified"))
      (node (ref "U2") (pin "4") (pinfunction "Vout_4") (pintype "unspecified"))
      (node (ref "U3") (pin "14") (pinfunction "3V3_14") (pintype "passive"))
      (node (ref "U4") (pin "8") (pinfunction "VCC_8") (pintype "unspecified"))
      (node (ref "U5") (pin "16") (pinfunction "VCC_16") (pintype "unspecified"))
      (node (ref "U5") (pin "4") (pinfunction "V3_4") (pintype "unspecified"))
    )
    (net (code "74") (name "unconnected-(LED22-DOUT-Pad2)") (class "Default")
      (node (ref "LED22") (pin "2") (pinfunction "DOUT_2") (pintype "unspecified+no_connect"))
    )
    (net (code "75") (name "unconnected-(SW1-Pad3)") (class "Default")
      (node (ref "SW1") (pin "3") (pinfunction "3_3") (pintype "unspecified+no_connect"))
    )
    (net (code "76") (name "unconnected-(SW2-Pad3)") (class "Default")
      (node (ref "SW2") (pin "3") (pinfunction "3_3") (pintype "unspecified+no_connect"))
    )
    (net (code "77") (name "unconnected-(U4-CS0-Pad17)") (class "Default")
      (node (ref "U4") (pin "17") (pinfunction "CS0_17") (pintype "unspecified+no_connect"))
    )
    (net (code "78") (name "unconnected-(U4-IO9-Pad19)") (class "Default")
      (node (ref "U4") (pin "19") (pinfunction "IO9_19") (pintype "unspecified+no_connect"))
    )
    (net (code "79") (name "unconnected-(U4-IO10-Pad20)") (class "Default")
      (node (ref "U4") (pin "20") (pinfunction "IO10_20") (pintype "unspecified+no_connect"))
    )
    (net (code "80") (name "unconnected-(U4-MISO-Pad18)") (class "Default")
      (node (ref "U4") (pin "18") (pinfunction "MISO_18") (pintype "unspecified+no_connect"))
    )
    (net (code "81") (name "unconnected-(U4-MOSI-Pad21)") (class "Default")
      (node (ref "U4") (pin "21") (pinfunction "MOSI_21") (pintype "unspecified+no_connect"))
    )
    (net (code "82") (name "unconnected-(U4-SCLK-Pad22)") (class "Default")
      (node (ref "U4") (pin "22") (pinfunction "SCLK_22") (pintype "unspecified+no_connect"))
    )
    (net (code "83") (name "unconnected-(U5-CTS#-Pad9)") (class "Default")
      (node (ref "U5") (pin "9") (pinfunction "CTS#_9") (pintype "unspecified+no_connect"))
    )
    (net (code "84") (name "unconnected-(U5-DCD#-Pad12)") (class "Default")
      (node (ref "U5") (pin "12") (pinfunction "DCD#_12") (pintype "unspecified+no_connect"))
    )
    (net (code "85") (name "unconnected-(U5-DSR#-Pad10)") (class "Default")
      (node (ref "U5") (pin "10") (pinfunction "DSR#_10") (pintype "unspecified+no_connect"))
    )
    (net (code "86") (name "unconnected-(U5-NC.-Pad7)") (class "Default")
      (node (ref "U5") (pin "7") (pinfunction "NC._7") (pintype "unspecified+no_connect"))
    )
    (net (code "87") (name "unconnected-(U5-NC.-Pad8)") (class "Default")
      (node (ref "U5") (pin "8") (pinfunction "NC._8") (pintype "unspecified+no_connect"))
    )
    (net (code "88") (name "unconnected-(U5-R232-Pad15)") (class "Default")
      (node (ref "U5") (pin "15") (pinfunction "R232_15") (pintype "unspecified+no_connect"))
    )
    (net (code "89") (name "unconnected-(U5-RI#-Pad11)") (class "Default")
      (node (ref "U5") (pin "11") (pinfunction "RI#_11") (pintype "unspecified+no_connect"))
    )
    (net (code "90") (name "unconnected-(USB3-ID-Pad4)") (class "Default")
      (node (ref "USB3") (pin "4") (pinfunction "ID_4") (pintype "unspecified+no_connect"))
    )
    (net (code "91") (name "unconnected-(USB4-ID-Pad4)") (class "Default")
      (node (ref "USB4") (pin "4") (pinfunction "ID_4") (pintype "unspecified+no_connect"))
    )
  )
)
